# Backplane.net
KiCad netlist of a schematic drawn in EAGLE
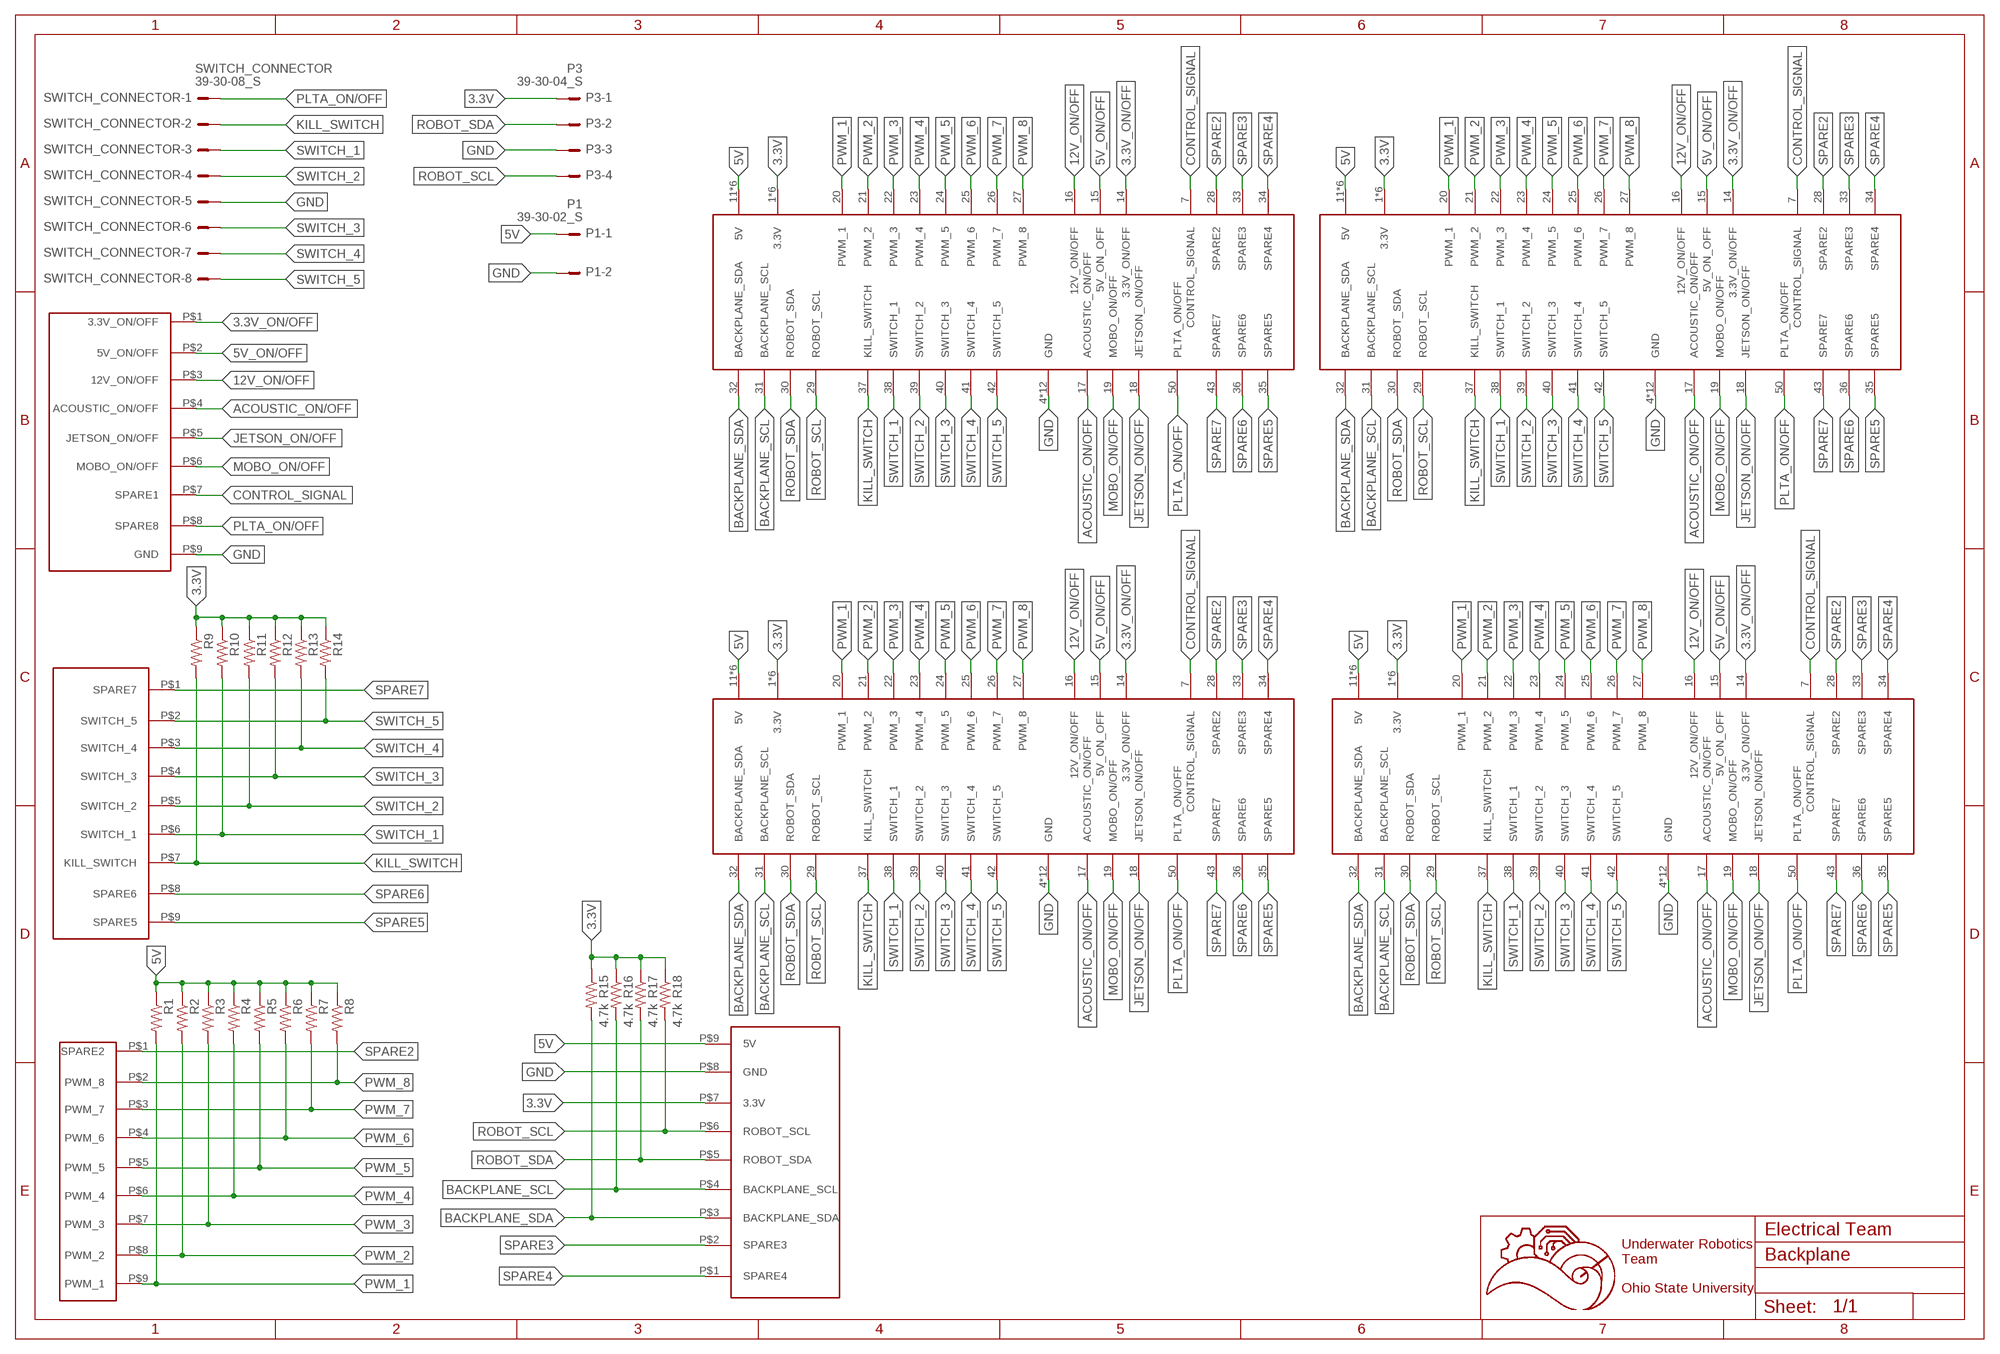
[diagram p0: schematic, sheet 1]

(export (version "E")
  (design (tool "Eeschema 10.0.6"))
  (components
    (comp (ref "P1")
      (value "39-30-02_S")
      (footprint "eagle-import:39-30-_02_")
      (libsource (lib "eagle-import") (part "39-30-?02?_S"))
    )
    (comp (ref "P3")
      (value "39-30-04_S")
      (footprint "eagle-import:39-30-_04_")
      (libsource (lib "eagle-import") (part "39-30-?04?_S"))
    )
    (comp (ref "R1")
      (value "R-US_R0603")
      (footprint "eagle-import:R0603")
      (libsource (lib "eagle-import") (part "R-US_R0603"))
    )
    (comp (ref "R2")
      (value "R-US_R0603")
      (footprint "eagle-import:R0603")
      (libsource (lib "eagle-import") (part "R-US_R0603"))
    )
    (comp (ref "R3")
      (value "R-US_R0603")
      (footprint "eagle-import:R0603")
      (libsource (lib "eagle-import") (part "R-US_R0603"))
    )
    (comp (ref "R4")
      (value "R-US_R0603")
      (footprint "eagle-import:R0603")
      (libsource (lib "eagle-import") (part "R-US_R0603"))
    )
    (comp (ref "R5")
      (value "R-US_R0603")
      (footprint "eagle-import:R0603")
      (libsource (lib "eagle-import") (part "R-US_R0603"))
    )
    (comp (ref "R6")
      (value "R-US_R0603")
      (footprint "eagle-import:R0603")
      (libsource (lib "eagle-import") (part "R-US_R0603"))
    )
    (comp (ref "R7")
      (value "R-US_R0603")
      (footprint "eagle-import:R0603")
      (libsource (lib "eagle-import") (part "R-US_R0603"))
    )
    (comp (ref "R8")
      (value "R-US_R0603")
      (footprint "eagle-import:R0603")
      (libsource (lib "eagle-import") (part "R-US_R0603"))
    )
    (comp (ref "R9")
      (value "R-US_R0603")
      (footprint "eagle-import:R0603")
      (libsource (lib "eagle-import") (part "R-US_R0603"))
    )
    (comp (ref "R10")
      (value "R-US_R0603")
      (footprint "eagle-import:R0603")
      (libsource (lib "eagle-import") (part "R-US_R0603"))
    )
    (comp (ref "R11")
      (value "R-US_R0603")
      (footprint "eagle-import:R0603")
      (libsource (lib "eagle-import") (part "R-US_R0603"))
    )
    (comp (ref "R12")
      (value "R-US_R0603")
      (footprint "eagle-import:R0603")
      (libsource (lib "eagle-import") (part "R-US_R0603"))
    )
    (comp (ref "R13")
      (value "R-US_R0603")
      (footprint "eagle-import:R0603")
      (libsource (lib "eagle-import") (part "R-US_R0603"))
    )
    (comp (ref "R14")
      (value "R-US_R0603")
      (footprint "eagle-import:R0603")
      (libsource (lib "eagle-import") (part "R-US_R0603"))
    )
    (comp (ref "R15")
      (value "4.7k")
      (footprint "eagle-import:R0603")
      (libsource (lib "eagle-import") (part "R-US_R0603"))
    )
    (comp (ref "R16")
      (value "4.7k")
      (footprint "eagle-import:R0603")
      (libsource (lib "eagle-import") (part "R-US_R0603"))
    )
    (comp (ref "R17")
      (value "4.7k")
      (footprint "eagle-import:R0603")
      (libsource (lib "eagle-import") (part "R-US_R0603"))
    )
    (comp (ref "R18")
      (value "4.7k")
      (footprint "eagle-import:R0603")
      (libsource (lib "eagle-import") (part "R-US_R0603"))
    )
    (comp (ref "SWITCH_CONNECTOR")
      (value "39-30-08_S")
      (footprint "eagle-import:39-30-_08_")
      (libsource (lib "eagle-import") (part "39-30-?08?_S"))
    )
    (comp (ref "U$1")
      (value "5530843-FEMALE")
      (footprint "eagle-import:5530843-6-BACKPLANEMATE")
      (libsource (lib "eagle-import") (part "5530843-FEMALE"))
    )
    (comp (ref "U$2")
      (value "5530843-FEMALE")
      (footprint "eagle-import:5530843-6-BACKPLANEMATE")
      (libsource (lib "eagle-import") (part "5530843-FEMALE"))
    )
    (comp (ref "U$3")
      (value "5530843-FEMALE")
      (footprint "eagle-import:5530843-6-BACKPLANEMATE")
      (libsource (lib "eagle-import") (part "5530843-FEMALE"))
    )
    (comp (ref "U$4")
      (value "5530843-FEMALE")
      (footprint "eagle-import:5530843-6-BACKPLANEMATE")
      (libsource (lib "eagle-import") (part "5530843-FEMALE"))
    )
    (comp (ref "U$5")
      (value "929870-01-09_1")
      (footprint "eagle-import:929852-01-09_1ROW")
      (libsource (lib "eagle-import") (part "929870-01-09_1"))
    )
    (comp (ref "U$6")
      (value "929870-01-09_2")
      (footprint "eagle-import:929852-01-09_1ROW")
      (libsource (lib "eagle-import") (part "929870-01-09_2"))
    )
    (comp (ref "U$7")
      (value "929870-01-09_3")
      (footprint "eagle-import:929852-01-09_1ROW")
      (libsource (lib "eagle-import") (part "929870-01-09_3"))
    )
    (comp (ref "U$8")
      (value "929870-01-09_4")
      (footprint "eagle-import:929852-01-09_1ROW")
      (libsource (lib "eagle-import") (part "929870-01-09_4"))
    )
  )
  (nets
    (net (code "1") (name "3.3V") (class "Default")
      (node (ref "P3") (pin "1") (pinfunction "P_1") (pintype "passive"))
      (node (ref "R10") (pin "1") (pinfunction "1_1") (pintype "passive"))
      (node (ref "R11") (pin "1") (pinfunction "1_1") (pintype "passive"))
      (node (ref "R12") (pin "1") (pinfunction "1_1") (pintype "passive"))
      (node (ref "R13") (pin "1") (pinfunction "1_1") (pintype "passive"))
      (node (ref "R14") (pin "1") (pinfunction "1_1") (pintype "passive"))
      (node (ref "R15") (pin "1") (pinfunction "1_1") (pintype "passive"))
      (node (ref "R16") (pin "1") (pinfunction "1_1") (pintype "passive"))
      (node (ref "R17") (pin "1") (pinfunction "1_1") (pintype "passive"))
      (node (ref "R18") (pin "1") (pinfunction "1_1") (pintype "passive"))
      (node (ref "R9") (pin "1") (pinfunction "1_1") (pintype "passive"))
      (node (ref "U$1") (pin "1") (pinfunction "3.3V_1") (pintype "bidirectional"))
      (node (ref "U$1") (pin "2") (pinfunction "3.3V_2") (pintype "bidirectional"))
      (node (ref "U$1") (pin "3") (pinfunction "3.3V_3") (pintype "bidirectional"))
      (node (ref "U$1") (pin "54") (pinfunction "3.3V_54") (pintype "bidirectional"))
      (node (ref "U$1") (pin "55") (pinfunction "3.3V_55") (pintype "bidirectional"))
      (node (ref "U$1") (pin "56") (pinfunction "3.3V_56") (pintype "bidirectional"))
      (node (ref "U$2") (pin "1") (pinfunction "3.3V_1") (pintype "bidirectional"))
      (node (ref "U$2") (pin "2") (pinfunction "3.3V_2") (pintype "bidirectional"))
      (node (ref "U$2") (pin "3") (pinfunction "3.3V_3") (pintype "bidirectional"))
      (node (ref "U$2") (pin "54") (pinfunction "3.3V_54") (pintype "bidirectional"))
      (node (ref "U$2") (pin "55") (pinfunction "3.3V_55") (pintype "bidirectional"))
      (node (ref "U$2") (pin "56") (pinfunction "3.3V_56") (pintype "bidirectional"))
      (node (ref "U$3") (pin "1") (pinfunction "3.3V_1") (pintype "bidirectional"))
      (node (ref "U$3") (pin "2") (pinfunction "3.3V_2") (pintype "bidirectional"))
      (node (ref "U$3") (pin "3") (pinfunction "3.3V_3") (pintype "bidirectional"))
      (node (ref "U$3") (pin "54") (pinfunction "3.3V_54") (pintype "bidirectional"))
      (node (ref "U$3") (pin "55") (pinfunction "3.3V_55") (pintype "bidirectional"))
      (node (ref "U$3") (pin "56") (pinfunction "3.3V_56") (pintype "bidirectional"))
      (node (ref "U$4") (pin "1") (pinfunction "3.3V_1") (pintype "bidirectional"))
      (node (ref "U$4") (pin "2") (pinfunction "3.3V_2") (pintype "bidirectional"))
      (node (ref "U$4") (pin "3") (pinfunction "3.3V_3") (pintype "bidirectional"))
      (node (ref "U$4") (pin "54") (pinfunction "3.3V_54") (pintype "bidirectional"))
      (node (ref "U$4") (pin "55") (pinfunction "3.3V_55") (pintype "bidirectional"))
      (node (ref "U$4") (pin "56") (pinfunction "3.3V_56") (pintype "bidirectional"))
      (node (ref "U$8") (pin "P$7") (pinfunction "3.3V_P$7") (pintype "bidirectional"))
    )
    (net (code "2") (name "3.3V_ON{slash}OFF") (class "Default")
      (node (ref "U$1") (pin "14") (pinfunction "3.3V_ON/OFF_14") (pintype "bidirectional"))
      (node (ref "U$2") (pin "14") (pinfunction "3.3V_ON/OFF_14") (pintype "bidirectional"))
      (node (ref "U$3") (pin "14") (pinfunction "3.3V_ON/OFF_14") (pintype "bidirectional"))
      (node (ref "U$4") (pin "14") (pinfunction "3.3V_ON/OFF_14") (pintype "bidirectional"))
      (node (ref "U$7") (pin "P$1") (pinfunction "3.3V_ON/OFF_P$1") (pintype "bidirectional"))
    )
    (net (code "3") (name "5V") (class "Default")
      (node (ref "P1") (pin "1") (pinfunction "P_1") (pintype "passive"))
      (node (ref "R1") (pin "1") (pinfunction "1_1") (pintype "passive"))
      (node (ref "R2") (pin "1") (pinfunction "1_1") (pintype "passive"))
      (node (ref "R3") (pin "1") (pinfunction "1_1") (pintype "passive"))
      (node (ref "R4") (pin "1") (pinfunction "1_1") (pintype "passive"))
      (node (ref "R5") (pin "1") (pinfunction "1_1") (pintype "passive"))
      (node (ref "R6") (pin "1") (pinfunction "1_1") (pintype "passive"))
      (node (ref "R7") (pin "1") (pinfunction "1_1") (pintype "passive"))
      (node (ref "R8") (pin "1") (pinfunction "1_1") (pintype "passive"))
      (node (ref "U$1") (pin "11") (pinfunction "5V_11") (pintype "bidirectional"))
      (node (ref "U$1") (pin "12") (pinfunction "5V_12") (pintype "bidirectional"))
      (node (ref "U$1") (pin "13") (pinfunction "5V_13") (pintype "bidirectional"))
      (node (ref "U$1") (pin "44") (pinfunction "5V_44") (pintype "bidirectional"))
      (node (ref "U$1") (pin "45") (pinfunction "5V_45") (pintype "bidirectional"))
      (node (ref "U$1") (pin "46") (pinfunction "5V_46") (pintype "bidirectional"))
      (node (ref "U$2") (pin "11") (pinfunction "5V_11") (pintype "bidirectional"))
      (node (ref "U$2") (pin "12") (pinfunction "5V_12") (pintype "bidirectional"))
      (node (ref "U$2") (pin "13") (pinfunction "5V_13") (pintype "bidirectional"))
      (node (ref "U$2") (pin "44") (pinfunction "5V_44") (pintype "bidirectional"))
      (node (ref "U$2") (pin "45") (pinfunction "5V_45") (pintype "bidirectional"))
      (node (ref "U$2") (pin "46") (pinfunction "5V_46") (pintype "bidirectional"))
      (node (ref "U$3") (pin "11") (pinfunction "5V_11") (pintype "bidirectional"))
      (node (ref "U$3") (pin "12") (pinfunction "5V_12") (pintype "bidirectional"))
      (node (ref "U$3") (pin "13") (pinfunction "5V_13") (pintype "bidirectional"))
      (node (ref "U$3") (pin "44") (pinfunction "5V_44") (pintype "bidirectional"))
      (node (ref "U$3") (pin "45") (pinfunction "5V_45") (pintype "bidirectional"))
      (node (ref "U$3") (pin "46") (pinfunction "5V_46") (pintype "bidirectional"))
      (node (ref "U$4") (pin "11") (pinfunction "5V_11") (pintype "bidirectional"))
      (node (ref "U$4") (pin "12") (pinfunction "5V_12") (pintype "bidirectional"))
      (node (ref "U$4") (pin "13") (pinfunction "5V_13") (pintype "bidirectional"))
      (node (ref "U$4") (pin "44") (pinfunction "5V_44") (pintype "bidirectional"))
      (node (ref "U$4") (pin "45") (pinfunction "5V_45") (pintype "bidirectional"))
      (node (ref "U$4") (pin "46") (pinfunction "5V_46") (pintype "bidirectional"))
      (node (ref "U$8") (pin "P$9") (pinfunction "5V_P$9") (pintype "bidirectional"))
    )
    (net (code "4") (name "5V_ON{slash}OFF") (class "Default")
      (node (ref "U$1") (pin "15") (pinfunction "5V_ON_OFF_15") (pintype "bidirectional"))
      (node (ref "U$2") (pin "15") (pinfunction "5V_ON_OFF_15") (pintype "bidirectional"))
      (node (ref "U$3") (pin "15") (pinfunction "5V_ON_OFF_15") (pintype "bidirectional"))
      (node (ref "U$4") (pin "15") (pinfunction "5V_ON_OFF_15") (pintype "bidirectional"))
      (node (ref "U$7") (pin "P$2") (pinfunction "5V_ON/OFF_P$2") (pintype "bidirectional"))
    )
    (net (code "5") (name "12V_ON{slash}OFF") (class "Default")
      (node (ref "U$1") (pin "16") (pinfunction "12V_ON/OFF_16") (pintype "bidirectional"))
      (node (ref "U$2") (pin "16") (pinfunction "12V_ON/OFF_16") (pintype "bidirectional"))
      (node (ref "U$3") (pin "16") (pinfunction "12V_ON/OFF_16") (pintype "bidirectional"))
      (node (ref "U$4") (pin "16") (pinfunction "12V_ON/OFF_16") (pintype "bidirectional"))
      (node (ref "U$7") (pin "P$3") (pinfunction "12V_ON/OFF_P$3") (pintype "bidirectional"))
    )
    (net (code "6") (name "ACOUSTIC_ON{slash}OFF") (class "Default")
      (node (ref "U$1") (pin "17") (pinfunction "ACOUSTIC_ON/OFF_17") (pintype "bidirectional"))
      (node (ref "U$2") (pin "17") (pinfunction "ACOUSTIC_ON/OFF_17") (pintype "bidirectional"))
      (node (ref "U$3") (pin "17") (pinfunction "ACOUSTIC_ON/OFF_17") (pintype "bidirectional"))
      (node (ref "U$4") (pin "17") (pinfunction "ACOUSTIC_ON/OFF_17") (pintype "bidirectional"))
      (node (ref "U$7") (pin "P$4") (pinfunction "ACOUSTIC_ON/OFF_P$4") (pintype "bidirectional"))
    )
    (net (code "7") (name "BACKPLANE_SCL") (class "Default")
      (node (ref "R16") (pin "2") (pinfunction "2_2") (pintype "passive"))
      (node (ref "U$1") (pin "31") (pinfunction "BACKPLANE_SCL_31") (pintype "bidirectional"))
      (node (ref "U$2") (pin "31") (pinfunction "BACKPLANE_SCL_31") (pintype "bidirectional"))
      (node (ref "U$3") (pin "31") (pinfunction "BACKPLANE_SCL_31") (pintype "bidirectional"))
      (node (ref "U$4") (pin "31") (pinfunction "BACKPLANE_SCL_31") (pintype "bidirectional"))
      (node (ref "U$8") (pin "P$4") (pinfunction "BACKPLANE_SCL_P$4") (pintype "bidirectional"))
    )
    (net (code "8") (name "BACKPLANE_SDA") (class "Default")
      (node (ref "R15") (pin "2") (pinfunction "2_2") (pintype "passive"))
      (node (ref "U$1") (pin "32") (pinfunction "BACKPLANE_SDA_32") (pintype "bidirectional"))
      (node (ref "U$2") (pin "32") (pinfunction "BACKPLANE_SDA_32") (pintype "bidirectional"))
      (node (ref "U$3") (pin "32") (pinfunction "BACKPLANE_SDA_32") (pintype "bidirectional"))
      (node (ref "U$4") (pin "32") (pinfunction "BACKPLANE_SDA_32") (pintype "bidirectional"))
      (node (ref "U$8") (pin "P$3") (pinfunction "BACKPLANE_SDA_P$3") (pintype "bidirectional"))
    )
    (net (code "9") (name "CONTROL_SIGNAL") (class "Default")
      (node (ref "U$1") (pin "7") (pinfunction "CONTROL_SIGNAL_7") (pintype "bidirectional"))
      (node (ref "U$2") (pin "7") (pinfunction "CONTROL_SIGNAL_7") (pintype "bidirectional"))
      (node (ref "U$3") (pin "7") (pinfunction "CONTROL_SIGNAL_7") (pintype "bidirectional"))
      (node (ref "U$4") (pin "7") (pinfunction "CONTROL_SIGNAL_7") (pintype "bidirectional"))
      (node (ref "U$7") (pin "P$7") (pinfunction "SPARE1_P$7") (pintype "bidirectional"))
    )
    (net (code "10") (name "GND") (class "Default")
      (node (ref "P1") (pin "2") (pinfunction "P_2") (pintype "passive"))
      (node (ref "P3") (pin "3") (pinfunction "P_3") (pintype "passive"))
      (node (ref "SWITCH_CONNECTOR") (pin "5") (pinfunction "P_5") (pintype "passive"))
      (node (ref "U$1") (pin "10") (pinfunction "GND_10") (pintype "bidirectional"))
      (node (ref "U$1") (pin "4") (pinfunction "GND_4") (pintype "bidirectional"))
      (node (ref "U$1") (pin "47") (pinfunction "GND_47") (pintype "bidirectional"))
      (node (ref "U$1") (pin "48") (pinfunction "GND_48") (pintype "bidirectional"))
      (node (ref "U$1") (pin "49") (pinfunction "GND_49") (pintype "bidirectional"))
      (node (ref "U$1") (pin "5") (pinfunction "GND_5") (pintype "bidirectional"))
      (node (ref "U$1") (pin "51") (pinfunction "GND_51") (pintype "bidirectional"))
      (node (ref "U$1") (pin "52") (pinfunction "GND_52") (pintype "bidirectional"))
      (node (ref "U$1") (pin "53") (pinfunction "GND_53") (pintype "bidirectional"))
      (node (ref "U$1") (pin "6") (pinfunction "GND_6") (pintype "bidirectional"))
      (node (ref "U$1") (pin "8") (pinfunction "GND_8") (pintype "bidirectional"))
      (node (ref "U$1") (pin "9") (pinfunction "GND_9") (pintype "bidirectional"))
      (node (ref "U$2") (pin "10") (pinfunction "GND_10") (pintype "bidirectional"))
      (node (ref "U$2") (pin "4") (pinfunction "GND_4") (pintype "bidirectional"))
      (node (ref "U$2") (pin "47") (pinfunction "GND_47") (pintype "bidirectional"))
      (node (ref "U$2") (pin "48") (pinfunction "GND_48") (pintype "bidirectional"))
      (node (ref "U$2") (pin "49") (pinfunction "GND_49") (pintype "bidirectional"))
      (node (ref "U$2") (pin "5") (pinfunction "GND_5") (pintype "bidirectional"))
      (node (ref "U$2") (pin "51") (pinfunction "GND_51") (pintype "bidirectional"))
      (node (ref "U$2") (pin "52") (pinfunction "GND_52") (pintype "bidirectional"))
      (node (ref "U$2") (pin "53") (pinfunction "GND_53") (pintype "bidirectional"))
      (node (ref "U$2") (pin "6") (pinfunction "GND_6") (pintype "bidirectional"))
      (node (ref "U$2") (pin "8") (pinfunction "GND_8") (pintype "bidirectional"))
      (node (ref "U$2") (pin "9") (pinfunction "GND_9") (pintype "bidirectional"))
      (node (ref "U$3") (pin "10") (pinfunction "GND_10") (pintype "bidirectional"))
      (node (ref "U$3") (pin "4") (pinfunction "GND_4") (pintype "bidirectional"))
      (node (ref "U$3") (pin "47") (pinfunction "GND_47") (pintype "bidirectional"))
      (node (ref "U$3") (pin "48") (pinfunction "GND_48") (pintype "bidirectional"))
      (node (ref "U$3") (pin "49") (pinfunction "GND_49") (pintype "bidirectional"))
      (node (ref "U$3") (pin "5") (pinfunction "GND_5") (pintype "bidirectional"))
      (node (ref "U$3") (pin "51") (pinfunction "GND_51") (pintype "bidirectional"))
      (node (ref "U$3") (pin "52") (pinfunction "GND_52") (pintype "bidirectional"))
      (node (ref "U$3") (pin "53") (pinfunction "GND_53") (pintype "bidirectional"))
      (node (ref "U$3") (pin "6") (pinfunction "GND_6") (pintype "bidirectional"))
      (node (ref "U$3") (pin "8") (pinfunction "GND_8") (pintype "bidirectional"))
      (node (ref "U$3") (pin "9") (pinfunction "GND_9") (pintype "bidirectional"))
      (node (ref "U$4") (pin "10") (pinfunction "GND_10") (pintype "bidirectional"))
      (node (ref "U$4") (pin "4") (pinfunction "GND_4") (pintype "bidirectional"))
      (node (ref "U$4") (pin "47") (pinfunction "GND_47") (pintype "bidirectional"))
      (node (ref "U$4") (pin "48") (pinfunction "GND_48") (pintype "bidirectional"))
      (node (ref "U$4") (pin "49") (pinfunction "GND_49") (pintype "bidirectional"))
      (node (ref "U$4") (pin "5") (pinfunction "GND_5") (pintype "bidirectional"))
      (node (ref "U$4") (pin "51") (pinfunction "GND_51") (pintype "bidirectional"))
      (node (ref "U$4") (pin "52") (pinfunction "GND_52") (pintype "bidirectional"))
      (node (ref "U$4") (pin "53") (pinfunction "GND_53") (pintype "bidirectional"))
      (node (ref "U$4") (pin "6") (pinfunction "GND_6") (pintype "bidirectional"))
      (node (ref "U$4") (pin "8") (pinfunction "GND_8") (pintype "bidirectional"))
      (node (ref "U$4") (pin "9") (pinfunction "GND_9") (pintype "bidirectional"))
      (node (ref "U$7") (pin "P$9") (pinfunction "GND_P$9") (pintype "bidirectional"))
      (node (ref "U$8") (pin "P$8") (pinfunction "GND_P$8") (pintype "bidirectional"))
    )
    (net (code "11") (name "JETSON_ON{slash}OFF") (class "Default")
      (node (ref "U$1") (pin "18") (pinfunction "JETSON_ON/OFF_18") (pintype "bidirectional"))
      (node (ref "U$2") (pin "18") (pinfunction "JETSON_ON/OFF_18") (pintype "bidirectional"))
      (node (ref "U$3") (pin "18") (pinfunction "JETSON_ON/OFF_18") (pintype "bidirectional"))
      (node (ref "U$4") (pin "18") (pinfunction "JETSON_ON/OFF_18") (pintype "bidirectional"))
      (node (ref "U$7") (pin "P$5") (pinfunction "JETSON_ON/OFF_P$5") (pintype "bidirectional"))
    )
    (net (code "12") (name "KILL_SWITCH") (class "Default")
      (node (ref "R9") (pin "2") (pinfunction "2_2") (pintype "passive"))
      (node (ref "SWITCH_CONNECTOR") (pin "2") (pinfunction "P_2") (pintype "passive"))
      (node (ref "U$1") (pin "37") (pinfunction "KILL_SWITCH_37") (pintype "output"))
      (node (ref "U$2") (pin "37") (pinfunction "KILL_SWITCH_37") (pintype "output"))
      (node (ref "U$3") (pin "37") (pinfunction "KILL_SWITCH_37") (pintype "output"))
      (node (ref "U$4") (pin "37") (pinfunction "KILL_SWITCH_37") (pintype "output"))
      (node (ref "U$5") (pin "P$7") (pinfunction "KILL_SWITCH_P$7") (pintype "bidirectional"))
    )
    (net (code "13") (name "MOBO_ON{slash}OFF") (class "Default")
      (node (ref "U$1") (pin "19") (pinfunction "MOBO_ON/OFF_19") (pintype "bidirectional"))
      (node (ref "U$2") (pin "19") (pinfunction "MOBO_ON/OFF_19") (pintype "bidirectional"))
      (node (ref "U$3") (pin "19") (pinfunction "MOBO_ON/OFF_19") (pintype "bidirectional"))
      (node (ref "U$4") (pin "19") (pinfunction "MOBO_ON/OFF_19") (pintype "bidirectional"))
      (node (ref "U$7") (pin "P$6") (pinfunction "MOBO_ON/OFF_P$6") (pintype "bidirectional"))
    )
    (net (code "14") (name "PLTA_ON{slash}OFF") (class "Default")
      (node (ref "SWITCH_CONNECTOR") (pin "1") (pinfunction "P_1") (pintype "passive"))
      (node (ref "U$1") (pin "50") (pinfunction "PLTA_ON/OFF_50") (pintype "bidirectional"))
      (node (ref "U$2") (pin "50") (pinfunction "PLTA_ON/OFF_50") (pintype "bidirectional"))
      (node (ref "U$3") (pin "50") (pinfunction "PLTA_ON/OFF_50") (pintype "bidirectional"))
      (node (ref "U$4") (pin "50") (pinfunction "PLTA_ON/OFF_50") (pintype "bidirectional"))
      (node (ref "U$7") (pin "P$8") (pinfunction "SPARE8_P$8") (pintype "bidirectional"))
    )
    (net (code "15") (name "PWM_1") (class "Default")
      (node (ref "R1") (pin "2") (pinfunction "2_2") (pintype "passive"))
      (node (ref "U$1") (pin "20") (pinfunction "PWM_1_20") (pintype "bidirectional"))
      (node (ref "U$2") (pin "20") (pinfunction "PWM_1_20") (pintype "bidirectional"))
      (node (ref "U$3") (pin "20") (pinfunction "PWM_1_20") (pintype "bidirectional"))
      (node (ref "U$4") (pin "20") (pinfunction "PWM_1_20") (pintype "bidirectional"))
      (node (ref "U$6") (pin "P$9") (pinfunction "PWM_1_P$9") (pintype "bidirectional"))
    )
    (net (code "16") (name "PWM_2") (class "Default")
      (node (ref "R2") (pin "2") (pinfunction "2_2") (pintype "passive"))
      (node (ref "U$1") (pin "21") (pinfunction "PWM_2_21") (pintype "bidirectional"))
      (node (ref "U$2") (pin "21") (pinfunction "PWM_2_21") (pintype "bidirectional"))
      (node (ref "U$3") (pin "21") (pinfunction "PWM_2_21") (pintype "bidirectional"))
      (node (ref "U$4") (pin "21") (pinfunction "PWM_2_21") (pintype "bidirectional"))
      (node (ref "U$6") (pin "P$8") (pinfunction "PWM_2_P$8") (pintype "bidirectional"))
    )
    (net (code "17") (name "PWM_3") (class "Default")
      (node (ref "R3") (pin "2") (pinfunction "2_2") (pintype "passive"))
      (node (ref "U$1") (pin "22") (pinfunction "PWM_3_22") (pintype "bidirectional"))
      (node (ref "U$2") (pin "22") (pinfunction "PWM_3_22") (pintype "bidirectional"))
      (node (ref "U$3") (pin "22") (pinfunction "PWM_3_22") (pintype "bidirectional"))
      (node (ref "U$4") (pin "22") (pinfunction "PWM_3_22") (pintype "bidirectional"))
      (node (ref "U$6") (pin "P$7") (pinfunction "PWM_3_P$7") (pintype "bidirectional"))
    )
    (net (code "18") (name "PWM_4") (class "Default")
      (node (ref "R4") (pin "2") (pinfunction "2_2") (pintype "passive"))
      (node (ref "U$1") (pin "23") (pinfunction "PWM_4_23") (pintype "bidirectional"))
      (node (ref "U$2") (pin "23") (pinfunction "PWM_4_23") (pintype "bidirectional"))
      (node (ref "U$3") (pin "23") (pinfunction "PWM_4_23") (pintype "bidirectional"))
      (node (ref "U$4") (pin "23") (pinfunction "PWM_4_23") (pintype "bidirectional"))
      (node (ref "U$6") (pin "P$6") (pinfunction "PWM_4_P$6") (pintype "bidirectional"))
    )
    (net (code "19") (name "PWM_5") (class "Default")
      (node (ref "R5") (pin "2") (pinfunction "2_2") (pintype "passive"))
      (node (ref "U$1") (pin "24") (pinfunction "PWM_5_24") (pintype "bidirectional"))
      (node (ref "U$2") (pin "24") (pinfunction "PWM_5_24") (pintype "bidirectional"))
      (node (ref "U$3") (pin "24") (pinfunction "PWM_5_24") (pintype "bidirectional"))
      (node (ref "U$4") (pin "24") (pinfunction "PWM_5_24") (pintype "bidirectional"))
      (node (ref "U$6") (pin "P$5") (pinfunction "PWM_5_P$5") (pintype "bidirectional"))
    )
    (net (code "20") (name "PWM_6") (class "Default")
      (node (ref "R6") (pin "2") (pinfunction "2_2") (pintype "passive"))
      (node (ref "U$1") (pin "25") (pinfunction "PWM_6_25") (pintype "bidirectional"))
      (node (ref "U$2") (pin "25") (pinfunction "PWM_6_25") (pintype "bidirectional"))
      (node (ref "U$3") (pin "25") (pinfunction "PWM_6_25") (pintype "bidirectional"))
      (node (ref "U$4") (pin "25") (pinfunction "PWM_6_25") (pintype "bidirectional"))
      (node (ref "U$6") (pin "P$4") (pinfunction "PWM_6_P$4") (pintype "bidirectional"))
    )
    (net (code "21") (name "PWM_7") (class "Default")
      (node (ref "R7") (pin "2") (pinfunction "2_2") (pintype "passive"))
      (node (ref "U$1") (pin "26") (pinfunction "PWM_7_26") (pintype "bidirectional"))
      (node (ref "U$2") (pin "26") (pinfunction "PWM_7_26") (pintype "bidirectional"))
      (node (ref "U$3") (pin "26") (pinfunction "PWM_7_26") (pintype "bidirectional"))
      (node (ref "U$4") (pin "26") (pinfunction "PWM_7_26") (pintype "bidirectional"))
      (node (ref "U$6") (pin "P$3") (pinfunction "PWM_7_P$3") (pintype "bidirectional"))
    )
    (net (code "22") (name "PWM_8") (class "Default")
      (node (ref "R8") (pin "2") (pinfunction "2_2") (pintype "passive"))
      (node (ref "U$1") (pin "27") (pinfunction "PWM_8_27") (pintype "bidirectional"))
      (node (ref "U$2") (pin "27") (pinfunction "PWM_8_27") (pintype "bidirectional"))
      (node (ref "U$3") (pin "27") (pinfunction "PWM_8_27") (pintype "bidirectional"))
      (node (ref "U$4") (pin "27") (pinfunction "PWM_8_27") (pintype "bidirectional"))
      (node (ref "U$6") (pin "P$2") (pinfunction "PWM_8_P$2") (pintype "bidirectional"))
    )
    (net (code "23") (name "ROBOT_SCL") (class "Default")
      (node (ref "P3") (pin "4") (pinfunction "P_4") (pintype "passive"))
      (node (ref "R18") (pin "2") (pinfunction "2_2") (pintype "passive"))
      (node (ref "U$1") (pin "29") (pinfunction "ROBOT_SCL_29") (pintype "bidirectional"))
      (node (ref "U$2") (pin "29") (pinfunction "ROBOT_SCL_29") (pintype "bidirectional"))
      (node (ref "U$3") (pin "29") (pinfunction "ROBOT_SCL_29") (pintype "bidirectional"))
      (node (ref "U$4") (pin "29") (pinfunction "ROBOT_SCL_29") (pintype "bidirectional"))
      (node (ref "U$8") (pin "P$6") (pinfunction "ROBOT_SCL_P$6") (pintype "bidirectional"))
    )
    (net (code "24") (name "ROBOT_SDA") (class "Default")
      (node (ref "P3") (pin "2") (pinfunction "P_2") (pintype "passive"))
      (node (ref "R17") (pin "2") (pinfunction "2_2") (pintype "passive"))
      (node (ref "U$1") (pin "30") (pinfunction "ROBOT_SDA_30") (pintype "bidirectional"))
      (node (ref "U$2") (pin "30") (pinfunction "ROBOT_SDA_30") (pintype "bidirectional"))
      (node (ref "U$3") (pin "30") (pinfunction "ROBOT_SDA_30") (pintype "bidirectional"))
      (node (ref "U$4") (pin "30") (pinfunction "ROBOT_SDA_30") (pintype "bidirectional"))
      (node (ref "U$8") (pin "P$5") (pinfunction "ROBOT_SDA_P$5") (pintype "bidirectional"))
    )
    (net (code "25") (name "SPARE2") (class "Default")
      (node (ref "U$1") (pin "28") (pinfunction "SPARE2_28") (pintype "bidirectional"))
      (node (ref "U$2") (pin "28") (pinfunction "SPARE2_28") (pintype "bidirectional"))
      (node (ref "U$3") (pin "28") (pinfunction "SPARE2_28") (pintype "bidirectional"))
      (node (ref "U$4") (pin "28") (pinfunction "SPARE2_28") (pintype "bidirectional"))
      (node (ref "U$6") (pin "P$1") (pinfunction "SPARE2_P$1") (pintype "bidirectional"))
    )
    (net (code "26") (name "SPARE3") (class "Default")
      (node (ref "U$1") (pin "33") (pinfunction "SPARE3_33") (pintype "bidirectional"))
      (node (ref "U$2") (pin "33") (pinfunction "SPARE3_33") (pintype "bidirectional"))
      (node (ref "U$3") (pin "33") (pinfunction "SPARE3_33") (pintype "bidirectional"))
      (node (ref "U$4") (pin "33") (pinfunction "SPARE3_33") (pintype "bidirectional"))
      (node (ref "U$8") (pin "P$2") (pinfunction "SPARE3_P$2") (pintype "bidirectional"))
    )
    (net (code "27") (name "SPARE4") (class "Default")
      (node (ref "U$1") (pin "34") (pinfunction "SPARE4_34") (pintype "bidirectional"))
      (node (ref "U$2") (pin "34") (pinfunction "SPARE4_34") (pintype "bidirectional"))
      (node (ref "U$3") (pin "34") (pinfunction "SPARE4_34") (pintype "bidirectional"))
      (node (ref "U$4") (pin "34") (pinfunction "SPARE4_34") (pintype "bidirectional"))
      (node (ref "U$8") (pin "P$1") (pinfunction "SPARE4_P$1") (pintype "bidirectional"))
    )
    (net (code "28") (name "SPARE5") (class "Default")
      (node (ref "U$1") (pin "35") (pinfunction "SPARE5_35") (pintype "bidirectional"))
      (node (ref "U$2") (pin "35") (pinfunction "SPARE5_35") (pintype "bidirectional"))
      (node (ref "U$3") (pin "35") (pinfunction "SPARE5_35") (pintype "bidirectional"))
      (node (ref "U$4") (pin "35") (pinfunction "SPARE5_35") (pintype "bidirectional"))
      (node (ref "U$5") (pin "P$9") (pinfunction "SPARE5_P$9") (pintype "bidirectional"))
    )
    (net (code "29") (name "SPARE6") (class "Default")
      (node (ref "U$1") (pin "36") (pinfunction "SPARE6_36") (pintype "bidirectional"))
      (node (ref "U$2") (pin "36") (pinfunction "SPARE6_36") (pintype "bidirectional"))
      (node (ref "U$3") (pin "36") (pinfunction "SPARE6_36") (pintype "bidirectional"))
      (node (ref "U$4") (pin "36") (pinfunction "SPARE6_36") (pintype "bidirectional"))
      (node (ref "U$5") (pin "P$8") (pinfunction "SPARE6_P$8") (pintype "bidirectional"))
    )
    (net (code "30") (name "SPARE7") (class "Default")
      (node (ref "U$1") (pin "43") (pinfunction "SPARE7_43") (pintype "bidirectional"))
      (node (ref "U$2") (pin "43") (pinfunction "SPARE7_43") (pintype "bidirectional"))
      (node (ref "U$3") (pin "43") (pinfunction "SPARE7_43") (pintype "bidirectional"))
      (node (ref "U$4") (pin "43") (pinfunction "SPARE7_43") (pintype "bidirectional"))
      (node (ref "U$5") (pin "P$1") (pinfunction "SPARE7_P$1") (pintype "bidirectional"))
    )
    (net (code "31") (name "SWITCH_1") (class "Default")
      (node (ref "R10") (pin "2") (pinfunction "2_2") (pintype "passive"))
      (node (ref "SWITCH_CONNECTOR") (pin "3") (pinfunction "P_3") (pintype "passive"))
      (node (ref "U$1") (pin "38") (pinfunction "SWITCH_1_38") (pintype "output"))
      (node (ref "U$2") (pin "38") (pinfunction "SWITCH_1_38") (pintype "output"))
      (node (ref "U$3") (pin "38") (pinfunction "SWITCH_1_38") (pintype "output"))
      (node (ref "U$4") (pin "38") (pinfunction "SWITCH_1_38") (pintype "output"))
      (node (ref "U$5") (pin "P$6") (pinfunction "SWITCH_1_P$6") (pintype "bidirectional"))
    )
    (net (code "32") (name "SWITCH_2") (class "Default")
      (node (ref "R11") (pin "2") (pinfunction "2_2") (pintype "passive"))
      (node (ref "SWITCH_CONNECTOR") (pin "4") (pinfunction "P_4") (pintype "passive"))
      (node (ref "U$1") (pin "39") (pinfunction "SWITCH_2_39") (pintype "output"))
      (node (ref "U$2") (pin "39") (pinfunction "SWITCH_2_39") (pintype "output"))
      (node (ref "U$3") (pin "39") (pinfunction "SWITCH_2_39") (pintype "output"))
      (node (ref "U$4") (pin "39") (pinfunction "SWITCH_2_39") (pintype "output"))
      (node (ref "U$5") (pin "P$5") (pinfunction "SWITCH_2_P$5") (pintype "bidirectional"))
    )
    (net (code "33") (name "SWITCH_3") (class "Default")
      (node (ref "R12") (pin "2") (pinfunction "2_2") (pintype "passive"))
      (node (ref "SWITCH_CONNECTOR") (pin "6") (pinfunction "P_6") (pintype "passive"))
      (node (ref "U$1") (pin "40") (pinfunction "SWITCH_3_40") (pintype "output"))
      (node (ref "U$2") (pin "40") (pinfunction "SWITCH_3_40") (pintype "output"))
      (node (ref "U$3") (pin "40") (pinfunction "SWITCH_3_40") (pintype "output"))
      (node (ref "U$4") (pin "40") (pinfunction "SWITCH_3_40") (pintype "output"))
      (node (ref "U$5") (pin "P$4") (pinfunction "SWITCH_3_P$4") (pintype "bidirectional"))
    )
    (net (code "34") (name "SWITCH_4") (class "Default")
      (node (ref "R13") (pin "2") (pinfunction "2_2") (pintype "passive"))
      (node (ref "SWITCH_CONNECTOR") (pin "7") (pinfunction "P_7") (pintype "passive"))
      (node (ref "U$1") (pin "41") (pinfunction "SWITCH_4_41") (pintype "output"))
      (node (ref "U$2") (pin "41") (pinfunction "SWITCH_4_41") (pintype "output"))
      (node (ref "U$3") (pin "41") (pinfunction "SWITCH_4_41") (pintype "output"))
      (node (ref "U$4") (pin "41") (pinfunction "SWITCH_4_41") (pintype "output"))
      (node (ref "U$5") (pin "P$3") (pinfunction "SWITCH_4_P$3") (pintype "bidirectional"))
    )
    (net (code "35") (name "SWITCH_5") (class "Default")
      (node (ref "R14") (pin "2") (pinfunction "2_2") (pintype "passive"))
      (node (ref "SWITCH_CONNECTOR") (pin "8") (pinfunction "P_8") (pintype "passive"))
      (node (ref "U$1") (pin "42") (pinfunction "SWITCH_5_42") (pintype "output"))
      (node (ref "U$2") (pin "42") (pinfunction "SWITCH_5_42") (pintype "output"))
      (node (ref "U$3") (pin "42") (pinfunction "SWITCH_5_42") (pintype "output"))
      (node (ref "U$4") (pin "42") (pinfunction "SWITCH_5_42") (pintype "output"))
      (node (ref "U$5") (pin "P$2") (pinfunction "SWITCH_5_P$2") (pintype "bidirectional"))
    )
  )
)
